# MP1584.net
KiCad netlist of a schematic drawn in Altium Designer
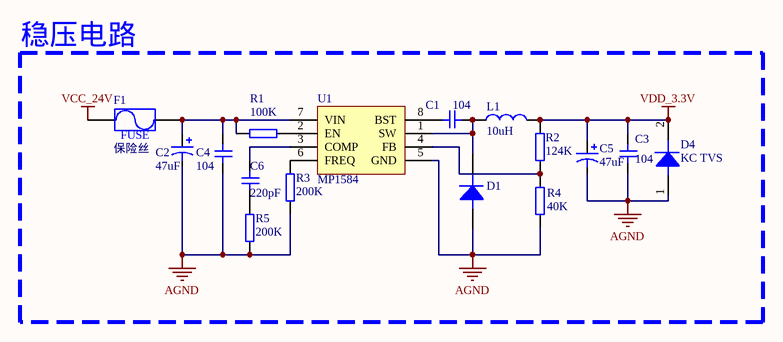
[diagram p0: MP1584.SchDoc]

(export (version "E")
  (design (tool "Eeschema 10.0.6"))
  (components
    (comp (ref "C1")
      (value "104")
      (footprint "0805C")
      (description "无极贴片电容")
      (libsource (lib "集大电协1.2") (part "Cap1"))
    )
    (comp (ref "C2")
      (value "47uF")
      (footprint "TAJ-B")
      (description "极性贴片电容")
      (libsource (lib "集大电协1.2") (part "Pol Cap"))
    )
    (comp (ref "C3")
      (value "104")
      (footprint "0805C")
      (description "无极贴片电容")
      (libsource (lib "集大电协1.2") (part "Cap1"))
    )
    (comp (ref "C4")
      (value "104")
      (footprint "0805C")
      (description "无极贴片电容")
      (libsource (lib "集大电协1.2") (part "Cap1"))
    )
    (comp (ref "C5")
      (value "47uF")
      (footprint "TAJ-B")
      (description "极性贴片电容")
      (libsource (lib "集大电协1.2") (part "Pol Cap"))
    )
    (comp (ref "C6")
      (value "220pF")
      (footprint "0805C")
      (description "无极贴片电容")
      (libsource (lib "集大电协1.2") (part "Cap1"))
    )
    (comp (ref "D1")
      (value "~")
      (footprint "SMBJ")
      (description "二极管")
      (libsource (lib "集大电协1.2") (part "Diode"))
    )
    (comp (ref "D4")
      (value "KC TVS")
      (footprint "SMBJ")
      (description "二极管")
      (libsource (lib "集大电协1.5") (part "Diode"))
    )
    (comp (ref "F1") (value "保险丝") (footprint "1812") (libsource (lib "集大电协1.2") (part "Fuse")))
    (comp (ref "L1")
      (value "10uH")
      (footprint "电感")
      (description "电感")
      (libsource (lib "集大电协1.2") (part "L"))
    )
    (comp (ref "R1")
      (value "100K")
      (footprint "0805R")
      (description "电阻")
      (libsource (lib "集大电协1.2") (part "Res"))
    )
    (comp (ref "R2")
      (value "124K")
      (footprint "0805R")
      (description "电阻")
      (libsource (lib "集大电协1.2") (part "Res"))
    )
    (comp (ref "R3")
      (value "200K")
      (footprint "0805R")
      (description "电阻")
      (libsource (lib "集大电协1.2") (part "Res"))
    )
    (comp (ref "R4")
      (value "40K")
      (footprint "0805R")
      (description "电阻")
      (libsource (lib "集大电协1.2") (part "Res"))
    )
    (comp (ref "R5")
      (value "200K")
      (footprint "0805R")
      (description "电阻")
      (libsource (lib "集大电协1.2") (part "Res"))
    )
    (comp (ref "U1") (value "MP1584") (libsource (lib "集大电协1.5") (part "MP1584")))
  )
  (nets
    (net (code "1") (name "AGND") (class "Default")
      (node (ref "C2") (pin "2") (pinfunction "2_2") (pintype "passive"))
      (node (ref "C3") (pin "1") (pinfunction "1_1") (pintype "passive"))
      (node (ref "C4") (pin "1") (pinfunction "1_1") (pintype "passive"))
      (node (ref "C5") (pin "2") (pinfunction "2_2") (pintype "passive"))
      (node (ref "D1") (pin "1") (pintype "passive"))
      (node (ref "D4") (pin "1") (pintype "passive"))
      (node (ref "R3") (pin "1") (pinfunction "1_1") (pintype "passive"))
      (node (ref "R4") (pin "1") (pinfunction "1_1") (pintype "passive"))
      (node (ref "R5") (pin "1") (pinfunction "1_1") (pintype "passive"))
      (node (ref "U1") (pin "5") (pinfunction "GND_5") (pintype "passive"))
    )
    (net (code "2") (name "Net-(C6-Pad1)") (class "Default")
      (node (ref "C6") (pin "1") (pinfunction "1_1") (pintype "passive"))
      (node (ref "R5") (pin "2") (pinfunction "2_2") (pintype "passive"))
    )
    (net (code "3") (name "Net-(U1-BST)") (class "Default")
      (node (ref "C1") (pin "2") (pinfunction "2_2") (pintype "passive"))
      (node (ref "U1") (pin "8") (pinfunction "BST_8") (pintype "passive"))
    )
    (net (code "4") (name "Net-(U1-COMP)") (class "Default")
      (node (ref "C6") (pin "2") (pinfunction "2_2") (pintype "passive"))
      (node (ref "U1") (pin "3") (pinfunction "COMP_3") (pintype "passive"))
    )
    (net (code "5") (name "Net-(U1-EN)") (class "Default")
      (node (ref "R1") (pin "2") (pinfunction "2_2") (pintype "passive"))
      (node (ref "U1") (pin "2") (pinfunction "EN_2") (pintype "passive"))
    )
    (net (code "6") (name "Net-(U1-FB)") (class "Default")
      (node (ref "R2") (pin "2") (pinfunction "2_2") (pintype "passive"))
      (node (ref "R4") (pin "2") (pinfunction "2_2") (pintype "passive"))
      (node (ref "U1") (pin "4") (pinfunction "FB_4") (pintype "passive"))
    )
    (net (code "7") (name "Net-(U1-FREQ)") (class "Default")
      (node (ref "R3") (pin "2") (pinfunction "2_2") (pintype "passive"))
      (node (ref "U1") (pin "6") (pinfunction "FREQ_6") (pintype "passive"))
    )
    (net (code "8") (name "Net-(U1-SW)") (class "Default")
      (node (ref "C1") (pin "1") (pinfunction "1_1") (pintype "passive"))
      (node (ref "D1") (pin "2") (pinfunction "2_2") (pintype "passive"))
      (node (ref "L1") (pin "1") (pinfunction "1_1") (pintype "passive"))
      (node (ref "U1") (pin "1") (pinfunction "SW_1") (pintype "passive"))
    )
    (net (code "9") (name "Net-(U1-VIN)") (class "Default")
      (node (ref "C2") (pin "1") (pinfunction "1_1") (pintype "passive"))
      (node (ref "C4") (pin "2") (pinfunction "2_2") (pintype "passive"))
      (node (ref "F1") (pin "2") (pinfunction "2_2") (pintype "passive"))
      (node (ref "R1") (pin "1") (pinfunction "1_1") (pintype "passive"))
      (node (ref "U1") (pin "7") (pinfunction "VIN_7") (pintype "passive"))
    )
    (net (code "10") (name "VCC_24V") (class "Default")
      (node (ref "F1") (pin "1") (pinfunction "1_1") (pintype "passive"))
    )
    (net (code "11") (name "VDD_3.3V") (class "Default")
      (node (ref "C3") (pin "2") (pinfunction "2_2") (pintype "passive"))
      (node (ref "C5") (pin "1") (pinfunction "1_1") (pintype "passive"))
      (node (ref "D4") (pin "2") (pinfunction "2_2") (pintype "passive"))
      (node (ref "L1") (pin "2") (pinfunction "2_2") (pintype "passive"))
      (node (ref "R2") (pin "1") (pinfunction "1_1") (pintype "passive"))
    )
  )
)
